# MicroController.net
KiCad netlist of a schematic drawn in Altium Designer
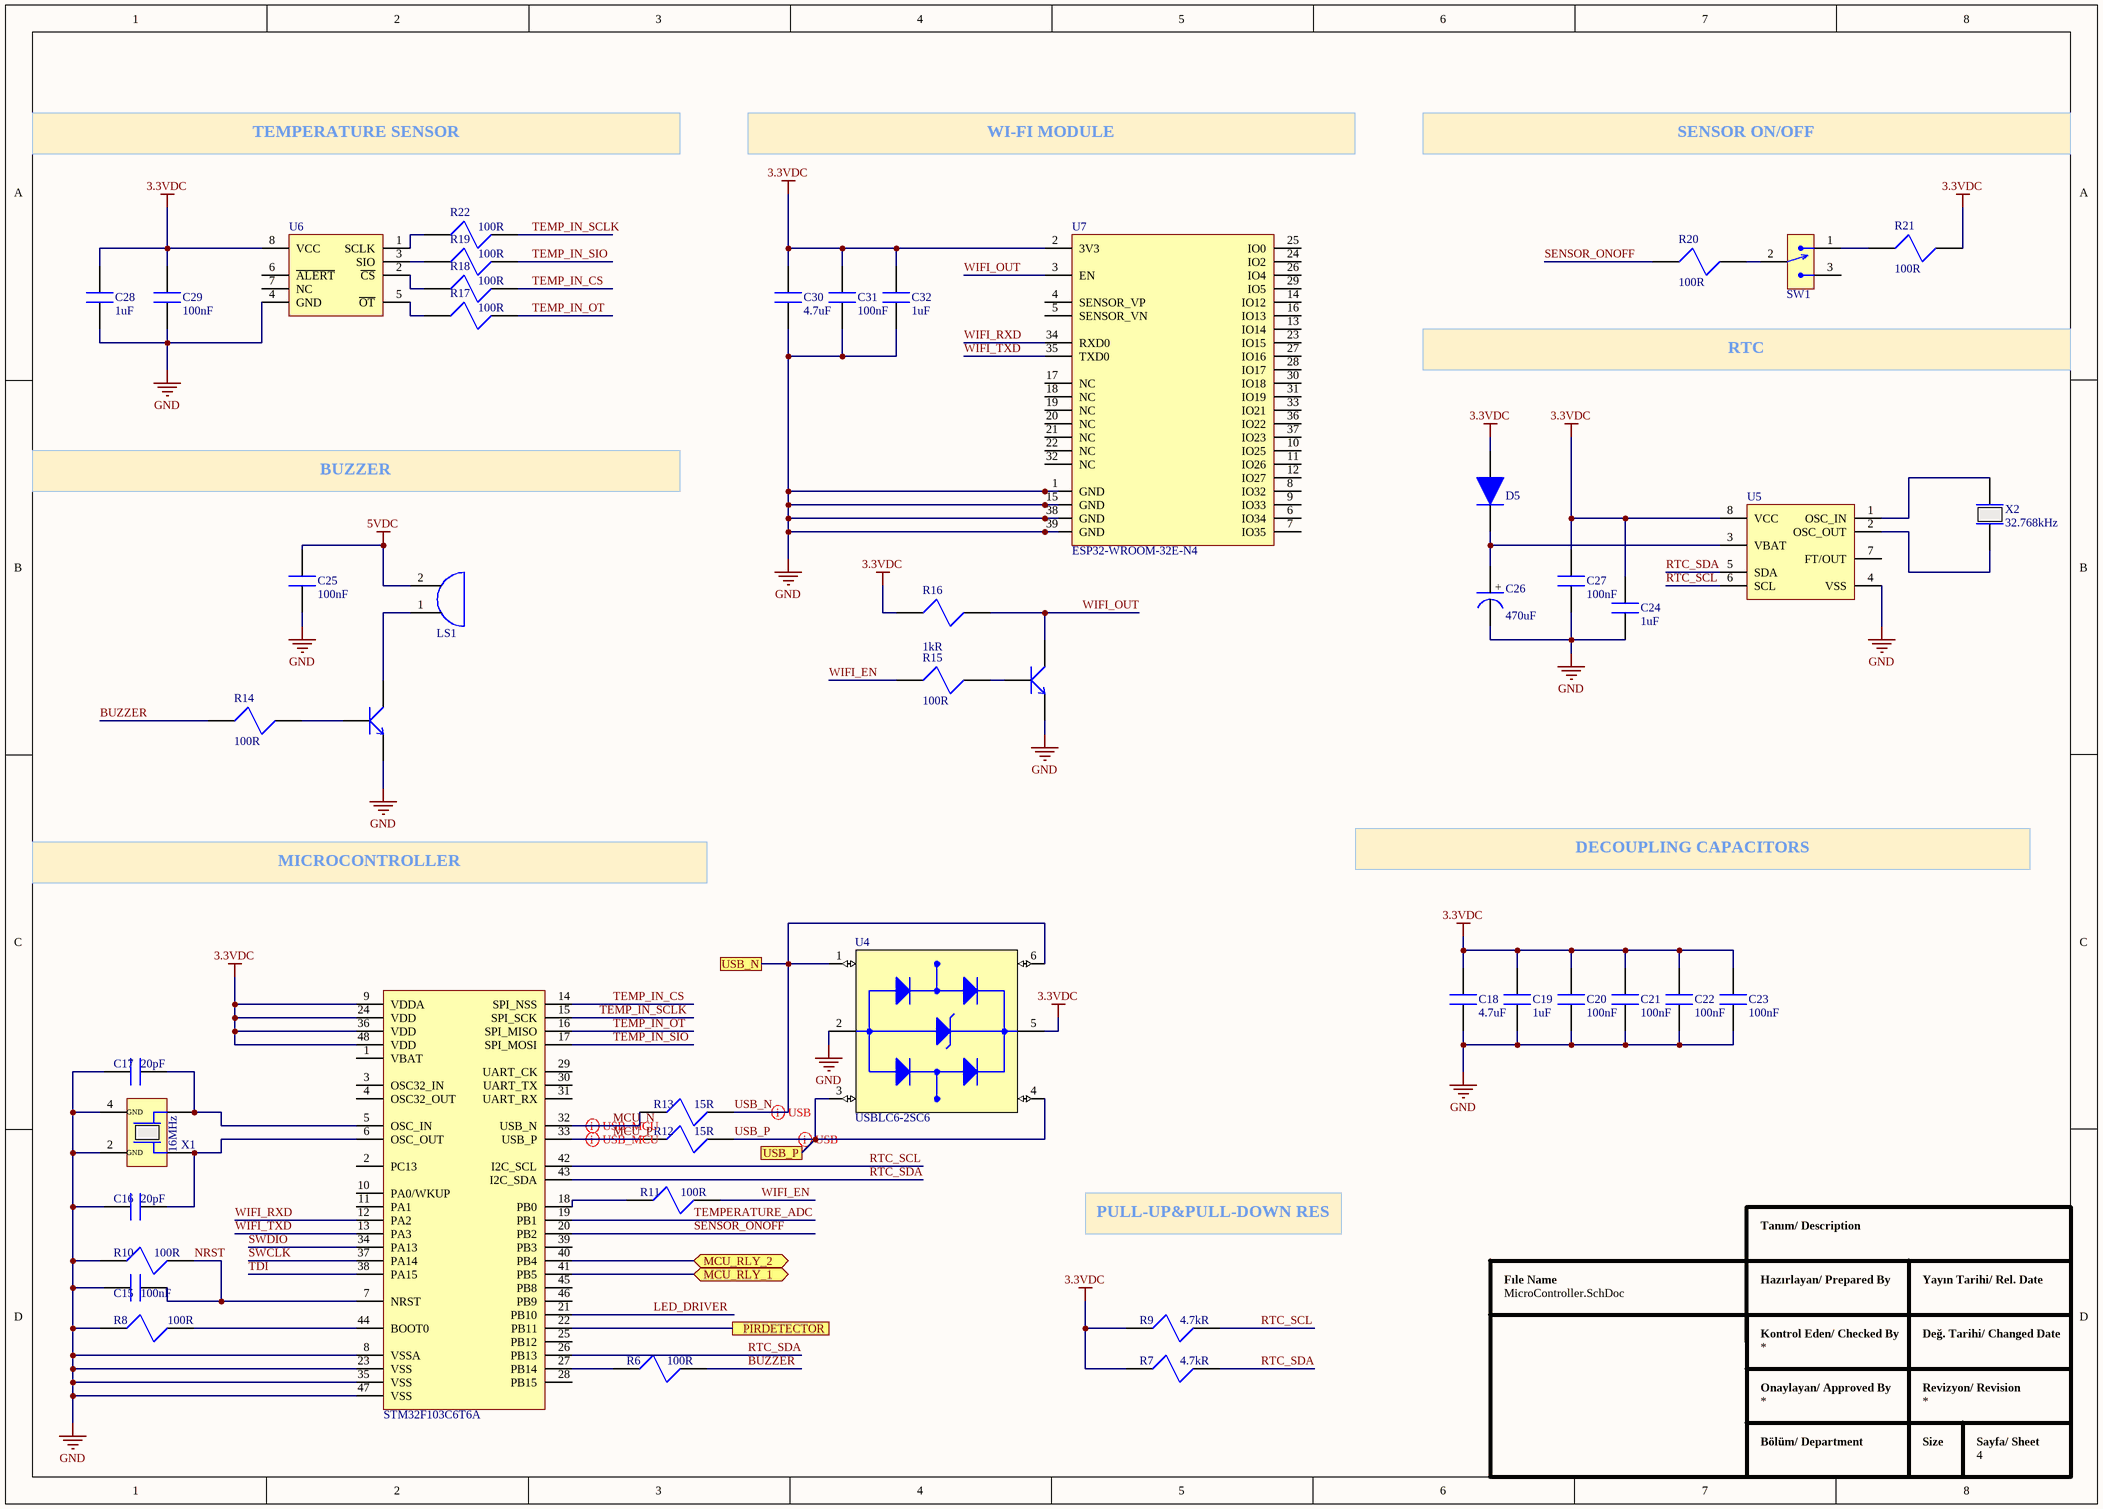
[diagram p0: MicroController.SchDoc]

(export (version "E")
  (design (tool "Eeschema 10.0.6"))
  (components
    (comp (ref "C15")
      (value "C0603C104M5RAC7867")
      (footprint "CAP_0603")
      (description "CAP CER 0.1UF 50V 20% X7R 0603")
      (fields
        (field (name "MANUFACTURER") "KEMET")
        (field (name "MANUFACTURER PART NUMBER") "C0603C104M5RACTU")
        (field (name "CAPACITANCE") "100nF")
        (field (name "DESIGNED BY") "Rumeysa Şahin")
      )
      (libsource (lib "Integrated_Library1") (part "CAP CER 100nF 0603"))
    )
    (comp (ref "C16")
      (value "CL10C200JB8NNNC")
      (footprint "CAP_0603")
      (description "CAP CER 20PF 50V C0G/NP0 0603")
      (fields
        (field (name "MANUFACTURER") "Samsung")
        (field (name "TOLERANCE") "5%")
        (field (name "CAPACITANCE") "20pF")
        (field (name "DESIGNED BY") "Rumeysa Şahin")
      )
      (libsource (lib "Integrated_Library1") (part "CAP CER 20pF 0603"))
    )
    (comp (ref "C17")
      (value "CL10C200JB8NNNC")
      (footprint "CAP_0603")
      (description "CAP CER 20PF 50V C0G/NP0 0603")
      (fields
        (field (name "MANUFACTURER") "Samsung")
        (field (name "TOLERANCE") "5%")
        (field (name "CAPACITANCE") "20pF")
        (field (name "DESIGNED BY") "Rumeysa Şahin")
      )
      (libsource (lib "Integrated_Library1") (part "CAP CER 20pF 0603"))
    )
    (comp (ref "C18")
      (value "CL21A475KAQNNNE")
      (footprint "CAP_0805")
      (description "CAP CER 4.7UF 25V X5R 0805")
      (fields
        (field (name "MANUFACTURER") "Samsung")
        (field (name "TOLERANCE") "10%")
        (field (name "CAPACITANCE") "4.7uF")
        (field (name "DESIGNED BY") "Rumeysa Şahin")
      )
      (libsource (lib "Integrated_Library1") (part "CAP CER 4.7uF 0805"))
    )
    (comp (ref "C19")
      (value "CL21B105KBFNNNE")
      (footprint "CAP_0805")
      (description "CAP CER 1UF 50V X7R 0805")
      (fields
        (field (name "MANUFACTURER") "Samsung")
        (field (name "TOLERANCE") "10%")
        (field (name "CAPACITANCE") "1uF")
        (field (name "DESIGNED BY") "Rumeysa Şahin")
      )
      (libsource (lib "Integrated_Library1") (part "CAP CER 1UF 0805"))
    )
    (comp (ref "C20")
      (value "C0603C104M5RAC7867")
      (footprint "CAP_0603")
      (description "CAP CER 0.1UF 50V 20% X7R 0603")
      (fields
        (field (name "MANUFACTURER") "KEMET")
        (field (name "MANUFACTURER PART NUMBER") "C0603C104M5RACTU")
        (field (name "CAPACITANCE") "100nF")
        (field (name "DESIGNED BY") "Rumeysa Şahin")
      )
      (libsource (lib "Integrated_Library1") (part "CAP CER 100nF 0603"))
    )
    (comp (ref "C21")
      (value "C0603C104M5RAC7867")
      (footprint "CAP_0603")
      (description "CAP CER 0.1UF 50V 20% X7R 0603")
      (fields
        (field (name "MANUFACTURER") "KEMET")
        (field (name "MANUFACTURER PART NUMBER") "C0603C104M5RACTU")
        (field (name "CAPACITANCE") "100nF")
        (field (name "DESIGNED BY") "Rumeysa Şahin")
      )
      (libsource (lib "Integrated_Library1") (part "CAP CER 100nF 0603"))
    )
    (comp (ref "C22")
      (value "C0603C104M5RAC7867")
      (footprint "CAP_0603")
      (description "CAP CER 0.1UF 50V 20% X7R 0603")
      (fields
        (field (name "MANUFACTURER") "KEMET")
        (field (name "MANUFACTURER PART NUMBER") "C0603C104M5RACTU")
        (field (name "CAPACITANCE") "100nF")
        (field (name "DESIGNED BY") "Rumeysa Şahin")
      )
      (libsource (lib "Integrated_Library1") (part "CAP CER 100nF 0603"))
    )
    (comp (ref "C23")
      (value "C0603C104M5RAC7867")
      (footprint "CAP_0603")
      (description "CAP CER 0.1UF 50V 20% X7R 0603")
      (fields
        (field (name "MANUFACTURER") "KEMET")
        (field (name "MANUFACTURER PART NUMBER") "C0603C104M5RACTU")
        (field (name "CAPACITANCE") "100nF")
        (field (name "DESIGNED BY") "Rumeysa Şahin")
      )
      (libsource (lib "Integrated_Library1") (part "CAP CER 100nF 0603"))
    )
    (comp (ref "C24")
      (value "CL21B105KBFNNNE")
      (footprint "CAP_0805")
      (description "CAP CER 1UF 50V X7R 0805")
      (fields
        (field (name "MANUFACTURER") "Samsung")
        (field (name "TOLERANCE") "10%")
        (field (name "CAPACITANCE") "1uF")
        (field (name "DESIGNED BY") "Rumeysa Şahin")
      )
      (libsource (lib "Integrated_Library1") (part "CAP CER 1UF 0805"))
    )
    (comp (ref "C25")
      (value "CL21B104KBCNNNC")
      (footprint "CAP_0805")
      (description "CAP CER 0.1UF 50V X7R 0805")
      (fields
        (field (name "MANUFACTURER") "Samsung")
        (field (name "TOLERANCE") "10%")
        (field (name "CAPACITANCE") "100nF")
        (field (name "DESIGNED BY") "Rumeysa Şahin")
      )
      (libsource (lib "Integrated_Library1") (part "CAP CER 100nF 0805"))
    )
    (comp (ref "C26")
      (value "ESH477M050AH4AA")
      (footprint "ESH477M050AH4AA")
      (description "Cap, 470UF, 50V, Alu Elec, Radial")
      (fields
        (field (name "MANUFACTURER") "KEMET")
        (field (name "TOLERANCE") "20%")
        (field (name "CAPACITANCE") "470uF")
        (field (name "DESIGNED BY") "Rumeysa Şahin")
      )
      (libsource (lib "Integrated_Library1") (part "CAP ALU 470uF"))
    )
    (comp (ref "C27")
      (value "CL21B104KBCNNNC")
      (footprint "CAP_0805")
      (description "CAP CER 0.1UF 50V X7R 0805")
      (fields
        (field (name "MANUFACTURER") "Samsung")
        (field (name "TOLERANCE") "10%")
        (field (name "CAPACITANCE") "100nF")
        (field (name "DESIGNED BY") "Rumeysa Şahin")
      )
      (libsource (lib "Integrated_Library1") (part "CAP CER 100nF 0805"))
    )
    (comp (ref "C28")
      (value "CL21B105KBFNNNE")
      (footprint "CAP_0805")
      (description "CAP CER 1UF 50V X7R 0805")
      (fields
        (field (name "MANUFACTURER") "Samsung")
        (field (name "TOLERANCE") "10%")
        (field (name "CAPACITANCE") "1uF")
        (field (name "DESIGNED BY") "Rumeysa Şahin")
      )
      (libsource (lib "Integrated_Library1") (part "CAP CER 1UF 0805"))
    )
    (comp (ref "C29")
      (value "CL21B104KBCNNNC")
      (footprint "CAP_0805")
      (description "CAP CER 0.1UF 50V X7R 0805")
      (fields
        (field (name "MANUFACTURER") "Samsung")
        (field (name "TOLERANCE") "10%")
        (field (name "CAPACITANCE") "100nF")
        (field (name "DESIGNED BY") "Rumeysa Şahin")
      )
      (libsource (lib "Integrated_Library1") (part "CAP CER 100nF 0805"))
    )
    (comp (ref "C30")
      (value "CL21A475KAQNNNE")
      (footprint "CAP_0805")
      (description "CAP CER 4.7UF 25V X5R 0805")
      (fields
        (field (name "MANUFACTURER") "Samsung")
        (field (name "TOLERANCE") "10%")
        (field (name "CAPACITANCE") "4.7uF")
        (field (name "DESIGNED BY") "Rumeysa Şahin")
      )
      (libsource (lib "Integrated_Library1") (part "CAP CER 4.7uF 0805"))
    )
    (comp (ref "C31")
      (value "CL21B104KBCNNNC")
      (footprint "CAP_0805")
      (description "CAP CER 0.1UF 50V X7R 0805")
      (fields
        (field (name "MANUFACTURER") "Samsung")
        (field (name "TOLERANCE") "10%")
        (field (name "CAPACITANCE") "100nF")
        (field (name "DESIGNED BY") "Rumeysa Şahin")
      )
      (libsource (lib "Integrated_Library1") (part "CAP CER 100nF 0805"))
    )
    (comp (ref "C32")
      (value "CL21B105KBFNNNE")
      (footprint "CAP_0805")
      (description "CAP CER 1UF 50V X7R 0805")
      (fields
        (field (name "MANUFACTURER") "Samsung")
        (field (name "TOLERANCE") "10%")
        (field (name "CAPACITANCE") "1uF")
        (field (name "DESIGNED BY") "Rumeysa Şahin")
      )
      (libsource (lib "Integrated_Library1") (part "CAP CER 1UF 0805"))
    )
    (comp (ref "D5")
      (value "1N4148WS")
      (footprint "SOD323F")
      (description "VR=75V IF=150mA Trr=4ns P=200mW")
      (fields
        (field (name "MANUFACTURER") "ON Semiconductor / Fairchild")
        (field (name "DESIGNED BY") "Rumeysa Şahin")
      )
      (libsource (lib "Integrated_Library1") (part "1N4148WS"))
    )
    (comp (ref "LS1")
      (value "CMI-9605IC-0580T")
      (footprint "CMI-9605IC-0580T")
      (description "Audio Buzzer Magnetic 3VDC 7VDC 30mA 5VDC 85dB 2600Hz to 2800Hz Through Hole Pin Box")
      (fields (field (name "MANUFACTURER") "CUI Devices") (field (name "DESIGNED BY") "Rumeysa Şahin"))
      (libsource (lib "Integrated_Library1") (part "CMI-9605IC-0580T"))
    )
    (comp (ref "Q3")
      (value "MMBT3904-7-F")
      (footprint "SOT23F")
      (description "NPN Ic=200mA Vceo=40V hfe=100~300 fT=310MHz P=300mW SOT-23")
      (fields (field (name "MANUFACTURER") "Diodes Zetex") (field (name "DESIGNED BY") "Rumeysa Şahin"))
      (libsource (lib "Integrated_Library1") (part "MMBT3904-7-F"))
    )
    (comp (ref "Q4")
      (value "MMBT3904-7-F")
      (footprint "SOT23F")
      (description "NPN Ic=200mA Vceo=40V hfe=100~300 fT=310MHz P=300mW SOT-23")
      (fields (field (name "MANUFACTURER") "Diodes Zetex") (field (name "DESIGNED BY") "Rumeysa Şahin"))
      (libsource (lib "Integrated_Library1") (part "MMBT3904-7-F"))
    )
    (comp (ref "R6")
      (value "RC0603JR-13100RL")
      (footprint "RES_0603")
      (description "Res Thick Film 0603 100 Ohm 5% 0.1W(1/10W) ±100ppm/C Pad SMD T/R")
      (fields
        (field (name "MANUFACTURER") "Yageo")
        (field (name "TOLERANCE") "5%")
        (field (name "RESISTANCE") "100R")
        (field (name "DESIGNED BY") "Rumeysa Şahin")
      )
      (libsource (lib "Integrated_Library1") (part "RES 100 OHM 0603"))
    )
    (comp (ref "R7")
      (value "RC0603FR-074K7L")
      (footprint "RES_0603")
      (description "Res Thick Film 0603 4.7K Ohm 1% 1/10W ±100ppm/°C Molded SMD Paper T/R")
      (fields
        (field (name "MANUFACTURER") "Yageo")
        (field (name "TOLERANCE") "1%")
        (field (name "RESISTANCE") "4.7kR")
        (field (name "DESIGNED BY") "Rumeysa Şahin")
      )
      (libsource (lib "Integrated_Library1") (part "RES 4K7R OHM 0603"))
    )
    (comp (ref "R8")
      (value "RC0603JR-13100RL")
      (footprint "RES_0603")
      (description "Res Thick Film 0603 100 Ohm 5% 0.1W(1/10W) ±100ppm/C Pad SMD T/R")
      (fields
        (field (name "MANUFACTURER") "Yageo")
        (field (name "TOLERANCE") "5%")
        (field (name "RESISTANCE") "100R")
        (field (name "DESIGNED BY") "Rumeysa Şahin")
      )
      (libsource (lib "Integrated_Library1") (part "RES 100 OHM 0603"))
    )
    (comp (ref "R9")
      (value "RC0603FR-074K7L")
      (footprint "RES_0603")
      (description "Res Thick Film 0603 4.7K Ohm 1% 1/10W ±100ppm/°C Molded SMD Paper T/R")
      (fields
        (field (name "MANUFACTURER") "Yageo")
        (field (name "TOLERANCE") "1%")
        (field (name "RESISTANCE") "4.7kR")
        (field (name "DESIGNED BY") "Rumeysa Şahin")
      )
      (libsource (lib "Integrated_Library1") (part "RES 4K7R OHM 0603"))
    )
    (comp (ref "R10")
      (value "RC0603JR-13100RL")
      (footprint "RES_0603")
      (description "Res Thick Film 0603 100 Ohm 5% 0.1W(1/10W) ±100ppm/C Pad SMD T/R")
      (fields
        (field (name "MANUFACTURER") "Yageo")
        (field (name "TOLERANCE") "5%")
        (field (name "RESISTANCE") "100R")
        (field (name "DESIGNED BY") "Rumeysa Şahin")
      )
      (libsource (lib "Integrated_Library1") (part "RES 100 OHM 0603"))
    )
    (comp (ref "R11")
      (value "RC0603JR-13100RL")
      (footprint "RES_0603")
      (description "Res Thick Film 0603 100 Ohm 5% 0.1W(1/10W) ±100ppm/C Pad SMD T/R")
      (fields
        (field (name "MANUFACTURER") "Yageo")
        (field (name "TOLERANCE") "5%")
        (field (name "RESISTANCE") "100R")
        (field (name "DESIGNED BY") "Rumeysa Şahin")
      )
      (libsource (lib "Integrated_Library1") (part "RES 100 OHM 0603"))
    )
    (comp (ref "R12")
      (value "RES 15 OHM 0603")
      (footprint "RES_0603")
      (description "Res Thick Film 0603 15 Ohm 5%")
      (fields
        (field (name "MANUFACTURER") "Yageo")
        (field (name "MANUFACTURER PART NUMBER") "RC0603JR-0715RL")
        (field (name "RESISTANCE") "15R")
        (field (name "DESIGNED BY") "Rumeysa Şahin")
      )
      (libsource (lib "Integrated_Library1") (part "RES 15 OHM 0603"))
    )
    (comp (ref "R13")
      (value "RES 15 OHM 0603")
      (footprint "RES_0603")
      (description "Res Thick Film 0603 15 Ohm 5%")
      (fields
        (field (name "MANUFACTURER") "Yageo")
        (field (name "MANUFACTURER PART NUMBER") "RC0603JR-0715RL")
        (field (name "RESISTANCE") "15R")
        (field (name "DESIGNED BY") "Rumeysa Şahin")
      )
      (libsource (lib "Integrated_Library1") (part "RES 15 OHM 0603"))
    )
    (comp (ref "R14")
      (value "RC0603JR-13100RL")
      (footprint "RES_0603")
      (description "Res Thick Film 0603 100 Ohm 5% 0.1W(1/10W) ±100ppm/C Pad SMD T/R")
      (fields
        (field (name "MANUFACTURER") "Yageo")
        (field (name "TOLERANCE") "5%")
        (field (name "RESISTANCE") "100R")
        (field (name "DESIGNED BY") "Rumeysa Şahin")
      )
      (libsource (lib "Integrated_Library1") (part "RES 100 OHM 0603"))
    )
    (comp (ref "R15")
      (value "RC0603JR-13100RL")
      (footprint "RES_0603")
      (description "Res Thick Film 0603 100 Ohm 5% 0.1W(1/10W) ±100ppm/C Pad SMD T/R")
      (fields
        (field (name "MANUFACTURER") "Yageo")
        (field (name "TOLERANCE") "5%")
        (field (name "RESISTANCE") "100R")
        (field (name "DESIGNED BY") "Rumeysa Şahin")
      )
      (libsource (lib "Integrated_Library1") (part "RES 100 OHM 0603"))
    )
    (comp (ref "R16")
      (value "RC0603FR-071KL")
      (footprint "RES_0603")
      (description "Res Thick Film 0603 1K Ohm 1% 1/10W ±100ppm/°C Molded SMD SMD Paper T/R")
      (fields
        (field (name "MANUFACTURER") "Yageo")
        (field (name "TOLERANCE") "1%")
        (field (name "RESISTANCE") "1kR")
        (field (name "DESIGNED BY") "Rumeysa Şahin")
      )
      (libsource (lib "Integrated_Library1") (part "RES 1K OHM 0603"))
    )
    (comp (ref "R17")
      (value "RC0603JR-13100RL")
      (footprint "RES_0603")
      (description "Res Thick Film 0603 100 Ohm 5% 0.1W(1/10W) ±100ppm/C Pad SMD T/R")
      (fields
        (field (name "MANUFACTURER") "Yageo")
        (field (name "TOLERANCE") "5%")
        (field (name "RESISTANCE") "100R")
        (field (name "DESIGNED BY") "Rumeysa Şahin")
      )
      (libsource (lib "Integrated_Library1") (part "RES 100 OHM 0603"))
    )
    (comp (ref "R18")
      (value "RC0603JR-13100RL")
      (footprint "RES_0603")
      (description "Res Thick Film 0603 100 Ohm 5% 0.1W(1/10W) ±100ppm/C Pad SMD T/R")
      (fields
        (field (name "MANUFACTURER") "Yageo")
        (field (name "TOLERANCE") "5%")
        (field (name "RESISTANCE") "100R")
        (field (name "DESIGNED BY") "Rumeysa Şahin")
      )
      (libsource (lib "Integrated_Library1") (part "RES 100 OHM 0603"))
    )
    (comp (ref "R19")
      (value "RC0603JR-13100RL")
      (footprint "RES_0603")
      (description "Res Thick Film 0603 100 Ohm 5% 0.1W(1/10W) ±100ppm/C Pad SMD T/R")
      (fields
        (field (name "MANUFACTURER") "Yageo")
        (field (name "TOLERANCE") "5%")
        (field (name "RESISTANCE") "100R")
        (field (name "DESIGNED BY") "Rumeysa Şahin")
      )
      (libsource (lib "Integrated_Library1") (part "RES 100 OHM 0603"))
    )
    (comp (ref "R20")
      (value "RC0603JR-13100RL")
      (footprint "RES_0603")
      (description "Res Thick Film 0603 100 Ohm 5% 0.1W(1/10W) ±100ppm/C Pad SMD T/R")
      (fields
        (field (name "MANUFACTURER") "Yageo")
        (field (name "TOLERANCE") "5%")
        (field (name "RESISTANCE") "100R")
        (field (name "DESIGNED BY") "Rumeysa Şahin")
      )
      (libsource (lib "Integrated_Library1") (part "RES 100 OHM 0603"))
    )
    (comp (ref "R21")
      (value "RC0603JR-13100RL")
      (footprint "RES_0603")
      (description "Res Thick Film 0603 100 Ohm 5% 0.1W(1/10W) ±100ppm/C Pad SMD T/R")
      (fields
        (field (name "MANUFACTURER") "Yageo")
        (field (name "TOLERANCE") "5%")
        (field (name "RESISTANCE") "100R")
        (field (name "DESIGNED BY") "Rumeysa Şahin")
      )
      (libsource (lib "Integrated_Library1") (part "RES 100 OHM 0603"))
    )
    (comp (ref "R22")
      (value "RC0603JR-13100RL")
      (footprint "RES_0603")
      (description "Res Thick Film 0603 100 Ohm 5% 0.1W(1/10W) ±100ppm/C Pad SMD T/R")
      (fields
        (field (name "MANUFACTURER") "Yageo")
        (field (name "TOLERANCE") "5%")
        (field (name "RESISTANCE") "100R")
        (field (name "DESIGNED BY") "Rumeysa Şahin")
      )
      (libsource (lib "Integrated_Library1") (part "RES 100 OHM 0603"))
    )
    (comp (ref "SW1")
      (value "EG1215AA")
      (footprint "EG1215AA")
      (description "Slide Switch, SPDT, 0.025A, 24V, SMD")
      (fields (field (name "MANUFACTURER") "E-Switch") (field (name "TOLERANCE") "4.95%"))
      (libsource (lib "Integrated_Library1") (part "EG1215AA"))
    )
    (comp (ref "U3")
      (value "STM32F103C6T6A")
      (footprint "LQFP-48")
      (description "MCU 32-bit STM32F ARM Cortex M3 RISC 32KB Flash 2.5V/3.3V 48-Pin LQFP Tray")
      (fields (field (name "MANUFACTURER") "STMicroelectronics") (field (name "DESIGNED BY") "Rumeysa Şahin"))
      (libsource (lib "Integrated_Library1") (part "STM32F103C6T6A"))
    )
    (comp (ref "U4")
      (value "USBLC6-2SC6")
      (footprint "SOT-23-6L")
      (description "TVS DIODE 5.25VWM 17VC SOT23-6")
      (fields (field (name "MANUFACTURER") "STMicroelectronics") (field (name "DESIGNED BY") "Rumeysa Şahin"))
      (libsource (lib "Integrated_Library1") (part "USB PROTECTION"))
    )
    (comp (ref "U5")
      (value "M41T0M6F")
      (footprint "SOIC-8")
      (description "M41T0 Series 2 to 5.5 V Serial I2C Real Time Clock Surface Mount - SOIC-8")
      (fields (field (name "MANUFACTURER") "STMicroelectronics") (field (name "DESIGNED BY") "Rumeysa Şahin"))
      (libsource (lib "Integrated_Library1") (part "M41T0M6F"))
    )
    (comp (ref "U6")
      (value "MAX6662MSA+")
      (footprint "SOIC-8")
      (description "Temp Sensor Digital Serial (3-Wire, SPI) 8-Pin SOIC N Tube")
      (fields (field (name "MANUFACTURER") "Maxim") (field (name "DESIGNED BY") "Rumeysa Şahin"))
      (libsource (lib "Integrated_Library1") (part "MAX6662MSA+"))
    )
    (comp (ref "U7")
      (value "ESP32-WROOM-32E-N4")
      (footprint "ESP32-32E")
      (description "Rx Txrx Mod Wifi Trace Ant SMD")
      (fields
        (field (name "MANUFACTURER") "Espressif Systems")
        (field (name "MANUFACTURER PART NUMBER") "ESP32-WROOM-32E(M113EH3200PH3Q0)")
        (field (name "DESIGNED BY") "Rumeysa Şahin")
      )
      (libsource (lib "Integrated_Library1") (part "ESP32-WROOM-32E-N4"))
    )
    (comp (ref "X1")
      (value "ECS-160-20-30B-TR")
      (footprint "ECS")
      (description "Crystal 16MHz ±30ppm (Tol) ±50ppm (Stability) 20pF FUND 50Ohm 4-Pin Mini-SMD T/R")
      (fields
        (field (name "MANUFACTURER") "ECS International")
        (field (name "TOLERANCE") "50ppm")
        (field (name "FREQUENCY") "16MHz")
        (field (name "DESIGNED BY") "Rumeysa Şahin")
      )
      (libsource (lib "Integrated_Library1") (part "CRYSTAL 16MHZ"))
    )
    (comp (ref "X2")
      (value "ABS05-32.768KHZ-T")
      (footprint "ABS05")
      (description "Crystal 0.032768MHz ±20ppm (Tol) 12.5pF Flexural 90000Ohm 2-Pin CSMD T/R")
      (fields
        (field (name "MANUFACTURER") "Abracon")
        (field (name "TOLERANCE") "20ppm")
        (field (name "FREQUENCY") "32.768kHz")
        (field (name "DESIGNED BY") "Rumeysa Şahin")
      )
      (libsource (lib "Integrated_Library1") (part "CRYSTAL 32768kHZ"))
    )
  )
  (nets
    (net (code "1") (name "/BUZZER") (class "Default")
      (node (ref "R14") (pin "1") (pintype "passive"))
      (node (ref "R6") (pin "2") (pinfunction "2_2") (pintype "passive"))
    )
    (net (code "2") (name "/LED_DRIVER") (class "Default")
      (node (ref "U3") (pin "21") (pinfunction "PB10_21") (pintype "passive"))
    )
    (net (code "3") (name "/MCU_N") (class "Default")
      (node (ref "R13") (pin "1") (pintype "passive"))
      (node (ref "U3") (pin "32") (pinfunction "USB_N_32") (pintype "passive"))
    )
    (net (code "4") (name "/MCU_P") (class "Default")
      (node (ref "R12") (pin "1") (pintype "passive"))
      (node (ref "U3") (pin "33") (pinfunction "USB_P_33") (pintype "passive"))
    )
    (net (code "5") (name "/MCU_RLY_1") (class "Default")
      (node (ref "U3") (pin "41") (pinfunction "PB5_41") (pintype "passive"))
    )
    (net (code "6") (name "/MCU_RLY_2") (class "Default")
      (node (ref "U3") (pin "40") (pinfunction "PB4_40") (pintype "passive"))
    )
    (net (code "7") (name "/NRST") (class "Default")
      (node (ref "C15") (pin "1") (pinfunction "1_1") (pintype "passive"))
      (node (ref "R10") (pin "2") (pinfunction "2_2") (pintype "passive"))
      (node (ref "U3") (pin "7") (pinfunction "NRST_7") (pintype "passive"))
    )
    (net (code "8") (name "/PIRDETECTOR") (class "Default")
      (node (ref "U3") (pin "22") (pinfunction "PB11_22") (pintype "passive"))
    )
    (net (code "9") (name "/RTC_SCL") (class "Default")
      (node (ref "R9") (pin "1") (pintype "passive"))
      (node (ref "U3") (pin "42") (pinfunction "I2C_SCL_42") (pintype "passive"))
      (node (ref "U5") (pin "6") (pinfunction "SCL_6") (pintype "passive"))
    )
    (net (code "10") (name "/RTC_SDA") (class "Default")
      (node (ref "R7") (pin "1") (pintype "passive"))
      (node (ref "U3") (pin "26") (pinfunction "PB13_26") (pintype "passive"))
      (node (ref "U3") (pin "43") (pinfunction "I2C_SDA_43") (pintype "passive"))
      (node (ref "U5") (pin "5") (pinfunction "SDA_5") (pintype "passive"))
    )
    (net (code "11") (name "/SENSOR_ONOFF") (class "Default")
      (node (ref "R20") (pin "1") (pintype "passive"))
      (node (ref "U3") (pin "20") (pinfunction "PB2_20") (pintype "passive"))
    )
    (net (code "12") (name "/SWCLK") (class "Default")
      (node (ref "U3") (pin "37") (pinfunction "PA14_37") (pintype "passive"))
    )
    (net (code "13") (name "/SWDIO") (class "Default")
      (node (ref "U3") (pin "34") (pinfunction "PA13_34") (pintype "passive"))
    )
    (net (code "14") (name "/TDI") (class "Default")
      (node (ref "U3") (pin "38") (pinfunction "PA15_38") (pintype "passive"))
    )
    (net (code "15") (name "/TEMPERATURE_ADC") (class "Default")
      (node (ref "U3") (pin "19") (pinfunction "PB1_19") (pintype "passive"))
    )
    (net (code "16") (name "/TEMP_IN_CS") (class "Default")
      (node (ref "R18") (pin "2") (pinfunction "2_2") (pintype "passive"))
      (node (ref "U3") (pin "14") (pinfunction "SPI_NSS_14") (pintype "passive"))
    )
    (net (code "17") (name "/TEMP_IN_OT") (class "Default")
      (node (ref "R17") (pin "2") (pinfunction "2_2") (pintype "passive"))
      (node (ref "U3") (pin "16") (pinfunction "SPI_MISO_16") (pintype "passive"))
    )
    (net (code "18") (name "/TEMP_IN_SCLK") (class "Default")
      (node (ref "R22") (pin "2") (pinfunction "2_2") (pintype "passive"))
      (node (ref "U3") (pin "15") (pinfunction "SPI_SCK_15") (pintype "passive"))
    )
    (net (code "19") (name "/TEMP_IN_SIO") (class "Default")
      (node (ref "R19") (pin "2") (pinfunction "2_2") (pintype "passive"))
      (node (ref "U3") (pin "17") (pinfunction "SPI_MOSI_17") (pintype "passive"))
    )
    (net (code "20") (name "/USB_N") (class "Default")
      (node (ref "R13") (pin "2") (pinfunction "2_2") (pintype "passive"))
      (node (ref "U4") (pin "1") (pinfunction "I/O1_IN_1") (pintype "bidirectional"))
      (node (ref "U4") (pin "6") (pinfunction "I/O1_OUT_6") (pintype "bidirectional"))
    )
    (net (code "21") (name "/USB_P") (class "Default")
      (node (ref "R12") (pin "2") (pinfunction "2_2") (pintype "passive"))
      (node (ref "U4") (pin "3") (pinfunction "I/O2_IN_3") (pintype "bidirectional"))
      (node (ref "U4") (pin "4") (pinfunction "I/O2_OUT_4") (pintype "bidirectional"))
    )
    (net (code "22") (name "/WIFI_EN") (class "Default")
      (node (ref "R11") (pin "2") (pinfunction "2_2") (pintype "passive"))
      (node (ref "R15") (pin "1") (pintype "passive"))
    )
    (net (code "23") (name "/WIFI_OUT") (class "Default")
      (node (ref "Q4") (pin "3") (pinfunction "C_3") (pintype "power_in"))
      (node (ref "R16") (pin "2") (pinfunction "2_2") (pintype "passive"))
      (node (ref "U7") (pin "3") (pinfunction "EN_3") (pintype "passive"))
    )
    (net (code "24") (name "/WIFI_RXD") (class "Default")
      (node (ref "U3") (pin "12") (pinfunction "PA2_12") (pintype "passive"))
      (node (ref "U7") (pin "34") (pinfunction "RXD0_34") (pintype "passive"))
    )
    (net (code "25") (name "/WIFI_TXD") (class "Default")
      (node (ref "U3") (pin "13") (pinfunction "PA3_13") (pintype "passive"))
      (node (ref "U7") (pin "35") (pinfunction "TXD0_35") (pintype "passive"))
    )
    (net (code "26") (name "3.3VDC") (class "Default")
      (node (ref "C18") (pin "2") (pinfunction "2_2") (pintype "passive"))
      (node (ref "C19") (pin "2") (pinfunction "2_2") (pintype "passive"))
      (node (ref "C20") (pin "2") (pinfunction "2_2") (pintype "passive"))
      (node (ref "C21") (pin "2") (pinfunction "2_2") (pintype "passive"))
      (node (ref "C22") (pin "2") (pinfunction "2_2") (pintype "passive"))
      (node (ref "C23") (pin "2") (pinfunction "2_2") (pintype "passive"))
      (node (ref "C24") (pin "2") (pinfunction "2_2") (pintype "passive"))
      (node (ref "C27") (pin "2") (pinfunction "2_2") (pintype "passive"))
      (node (ref "C28") (pin "2") (pinfunction "2_2") (pintype "passive"))
      (node (ref "C29") (pin "2") (pinfunction "2_2") (pintype "passive"))
      (node (ref "C30") (pin "2") (pinfunction "2_2") (pintype "passive"))
      (node (ref "C31") (pin "2") (pinfunction "2_2") (pintype "passive"))
      (node (ref "C32") (pin "2") (pinfunction "2_2") (pintype "passive"))
      (node (ref "D5") (pin "2") (pinfunction "2_2") (pintype "power_in"))
      (node (ref "R16") (pin "1") (pintype "passive"))
      (node (ref "R21") (pin "2") (pinfunction "2_2") (pintype "passive"))
      (node (ref "R7") (pin "2") (pinfunction "2_2") (pintype "passive"))
      (node (ref "R9") (pin "2") (pinfunction "2_2") (pintype "passive"))
      (node (ref "U3") (pin "24") (pinfunction "VDD_24") (pintype "passive"))
      (node (ref "U3") (pin "36") (pinfunction "VDD_36") (pintype "passive"))
      (node (ref "U3") (pin "48") (pinfunction "VDD_48") (pintype "passive"))
      (node (ref "U3") (pin "9") (pinfunction "VDDA_9") (pintype "passive"))
      (node (ref "U4") (pin "5") (pinfunction "VBUS_5") (pintype "power_in"))
      (node (ref "U5") (pin "8") (pinfunction "VCC_8") (pintype "passive"))
      (node (ref "U6") (pin "8") (pinfunction "VCC_8") (pintype "passive"))
      (node (ref "U7") (pin "2") (pinfunction "3V3_2") (pintype "passive"))
    )
    (net (code "27") (name "5VDC") (class "Default")
      (node (ref "C25") (pin "2") (pinfunction "2_2") (pintype "passive"))
      (node (ref "LS1") (pin "2") (pinfunction "2_2") (pintype "passive"))
    )
    (net (code "28") (name "GND") (class "Default")
      (node (ref "C15") (pin "2") (pinfunction "2_2") (pintype "passive"))
      (node (ref "C16") (pin "2") (pinfunction "2_2") (pintype "passive"))
      (node (ref "C17") (pin "2") (pinfunction "2_2") (pintype "passive"))
      (node (ref "C18") (pin "1") (pinfunction "1_1") (pintype "passive"))
      (node (ref "C19") (pin "1") (pinfunction "1_1") (pintype "passive"))
      (node (ref "C20") (pin "1") (pinfunction "1_1") (pintype "passive"))
      (node (ref "C21") (pin "1") (pinfunction "1_1") (pintype "passive"))
      (node (ref "C22") (pin "1") (pinfunction "1_1") (pintype "passive"))
      (node (ref "C23") (pin "1") (pinfunction "1_1") (pintype "passive"))
      (node (ref "C24") (pin "1") (pinfunction "1_1") (pintype "passive"))
      (node (ref "C25") (pin "1") (pinfunction "1_1") (pintype "passive"))
      (node (ref "C26") (pin "2") (pinfunction "2_2") (pintype "passive"))
      (node (ref "C27") (pin "1") (pinfunction "1_1") (pintype "passive"))
      (node (ref "C28") (pin "1") (pinfunction "1_1") (pintype "passive"))
      (node (ref "C29") (pin "1") (pinfunction "1_1") (pintype "passive"))
      (node (ref "C30") (pin "1") (pinfunction "1_1") (pintype "passive"))
      (node (ref "C31") (pin "1") (pinfunction "1_1") (pintype "passive"))
      (node (ref "C32") (pin "1") (pinfunction "1_1") (pintype "passive"))
      (node (ref "Q3") (pin "2") (pinfunction "E_2") (pintype "power_in"))
      (node (ref "Q4") (pin "2") (pinfunction "E_2") (pintype "power_in"))
      (node (ref "R10") (pin "1") (pintype "passive"))
      (node (ref "R8") (pin "1") (pintype "passive"))
      (node (ref "U3") (pin "23") (pinfunction "VSS_23") (pintype "passive"))
      (node (ref "U3") (pin "35") (pinfunction "VSS_35") (pintype "passive"))
      (node (ref "U3") (pin "47") (pinfunction "VSS_47") (pintype "passive"))
      (node (ref "U3") (pin "8") (pinfunction "VSSA_8") (pintype "passive"))
      (node (ref "U4") (pin "2") (pinfunction "GND_2") (pintype "power_in"))
      (node (ref "U5") (pin "4") (pinfunction "VSS_4") (pintype "passive"))
      (node (ref "U6") (pin "4") (pinfunction "GND_4") (pintype "passive"))
      (node (ref "U7") (pin "1") (pinfunction "GND_1") (pintype "passive"))
      (node (ref "U7") (pin "15") (pinfunction "GND_15") (pintype "passive"))
      (node (ref "U7") (pin "38") (pinfunction "GND_38") (pintype "passive"))
      (node (ref "U7") (pin "39") (pinfunction "GND_39") (pintype "passive"))
      (node (ref "X1") (pin "2") (pinfunction "GND_2") (pintype "passive"))
      (node (ref "X1") (pin "4") (pinfunction "GND_4") (pintype "passive"))
    )
    (net (code "29") (name "Net-(Q3-B)") (class "Default")
      (node (ref "Q3") (pin "1") (pinfunction "B_1") (pintype "power_in"))
      (node (ref "R14") (pin "2") (pinfunction "2_2") (pintype "passive"))
    )
    (net (code "30") (name "Net-(Q3-C)") (class "Default")
      (node (ref "LS1") (pin "1") (pinfunction "1_1") (pintype "passive"))
      (node (ref "Q3") (pin "3") (pinfunction "C_3") (pintype "power_in"))
    )
    (net (code "31") (name "Net-(Q4-B)") (class "Default")
      (node (ref "Q4") (pin "1") (pinfunction "B_1") (pintype "power_in"))
      (node (ref "R15") (pin "2") (pinfunction "2_2") (pintype "passive"))
    )
    (net (code "32") (name "Net-(R20-Pad2)") (class "Default")
      (node (ref "R20") (pin "2") (pinfunction "2_2") (pintype "passive"))
      (node (ref "SW1") (pin "2") (pinfunction "2_2") (pintype "passive"))
    )
    (net (code "33") (name "Net-(R21-Pad1)") (class "Default")
      (node (ref "R21") (pin "1") (pintype "passive"))
      (node (ref "SW1") (pin "1") (pinfunction "1_1") (pintype "passive"))
    )
    (net (code "34") (name "Net-(U3-BOOT0)") (class "Default")
      (node (ref "R8") (pin "2") (pinfunction "2_2") (pintype "passive"))
      (node (ref "U3") (pin "44") (pinfunction "BOOT0_44") (pintype "passive"))
    )
    (net (code "35") (name "Net-(U3-OSC_IN)") (class "Default")
      (node (ref "C17") (pin "1") (pinfunction "1_1") (pintype "passive"))
      (node (ref "U3") (pin "5") (pinfunction "OSC_IN_5") (pintype "passive"))
      (node (ref "X1") (pin "3") (pinfunction "3_3") (pintype "passive"))
    )
    (net (code "36") (name "Net-(U3-OSC_OUT)") (class "Default")
      (node (ref "C16") (pin "1") (pinfunction "1_1") (pintype "passive"))
      (node (ref "U3") (pin "6") (pinfunction "OSC_OUT_6") (pintype "passive"))
      (node (ref "X1") (pin "1") (pinfunction "1_1") (pintype "passive"))
    )
    (net (code "37") (name "Net-(U3-PB0)") (class "Default")
      (node (ref "R11") (pin "1") (pintype "passive"))
      (node (ref "U3") (pin "18") (pinfunction "PB0_18") (pintype "passive"))
    )
    (net (code "38") (name "Net-(U3-PB14)") (class "Default")
      (node (ref "R6") (pin "1") (pintype "passive"))
      (node (ref "U3") (pin "27") (pinfunction "PB14_27") (pintype "passive"))
    )
    (net (code "39") (name "Net-(U5-OSC_IN)") (class "Default")
      (node (ref "U5") (pin "1") (pinfunction "OSC_IN_1") (pintype "passive"))
      (node (ref "X2") (pin "2") (pinfunction "2_2") (pintype "passive"))
    )
    (net (code "40") (name "Net-(U5-OSC_OUT)") (class "Default")
      (node (ref "U5") (pin "2") (pinfunction "OSC_OUT_2") (pintype "passive"))
      (node (ref "X2") (pin "1") (pinfunction "1_1") (pintype "passive"))
    )
    (net (code "41") (name "Net-(U5-VBAT)") (class "Default")
      (node (ref "C26") (pin "1") (pinfunction "1_1") (pintype "passive"))
      (node (ref "D5") (pin "1") (pinfunction "1_1") (pintype "power_in"))
      (node (ref "U5") (pin "3") (pinfunction "VBAT_3") (pintype "passive"))
    )
    (net (code "42") (name "Net-(U6-SCLK)") (class "Default")
      (node (ref "R22") (pin "1") (pintype "passive"))
      (node (ref "U6") (pin "1") (pinfunction "SCLK_1") (pintype "passive"))
    )
    (net (code "43") (name "Net-(U6-SIO)") (class "Default")
      (node (ref "R19") (pin "1") (pintype "passive"))
      (node (ref "U6") (pin "3") (pinfunction "SIO_3") (pintype "passive"))
    )
    (net (code "44") (name "Net-(U6-~{CS})") (class "Default")
      (node (ref "R18") (pin "1") (pintype "passive"))
      (node (ref "U6") (pin "2") (pinfunction "~{CS}_2") (pintype "passive"))
    )
    (net (code "45") (name "Net-(U6-~{OT})") (class "Default")
      (node (ref "R17") (pin "1") (pintype "passive"))
      (node (ref "U6") (pin "5") (pinfunction "~{OT}_5") (pintype "passive"))
    )
    (net (code "46") (name "unconnected-(SW1-Pad3)") (class "Default")
      (node (ref "SW1") (pin "3") (pinfunction "3_3") (pintype "passive"))
    )
    (net (code "47") (name "unconnected-(U3-OSC32_IN-Pad3)") (class "Default")
      (node (ref "U3") (pin "3") (pinfunction "OSC32_IN_3") (pintype "passive"))
    )
    (net (code "48") (name "unconnected-(U3-OSC32_OUT-Pad4)") (class "Default")
      (node (ref "U3") (pin "4") (pinfunction "OSC32_OUT_4") (pintype "passive"))
    )
    (net (code "49") (name "unconnected-(U3-PA0{slash}WKUP-Pad10)") (class "Default")
      (node (ref "U3") (pin "10") (pinfunction "PA0/WKUP_10") (pintype "passive"))
    )
    (net (code "50") (name "unconnected-(U3-PA1-Pad11)") (class "Default")
      (node (ref "U3") (pin "11") (pinfunction "PA1_11") (pintype "passive"))
    )
    (net (code "51") (name "unconnected-(U3-PB3-Pad39)") (class "Default")
      (node (ref "U3") (pin "39") (pinfunction "PB3_39") (pintype "passive"))
    )
    (net (code "52") (name "unconnected-(U3-PB8-Pad45)") (class "Default")
      (node (ref "U3") (pin "45") (pinfunction "PB8_45") (pintype "passive"))
    )
    (net (code "53") (name "unconnected-(U3-PB9-Pad46)") (class "Default")
      (node (ref "U3") (pin "46") (pinfunction "PB9_46") (pintype "passive"))
    )
    (net (code "54") (name "unconnected-(U3-PB12-Pad25)") (class "Default")
      (node (ref "U3") (pin "25") (pinfunction "PB12_25") (pintype "passive"))
    )
    (net (code "55") (name "unconnected-(U3-PB15-Pad28)") (class "Default")
      (node (ref "U3") (pin "28") (pinfunction "PB15_28") (pintype "passive"))
    )
    (net (code "56") (name "unconnected-(U3-PC13-Pad2)") (class "Default")
      (node (ref "U3") (pin "2") (pinfunction "PC13_2") (pintype "passive"))
    )
    (net (code "57") (name "unconnected-(U3-UART_CK-Pad29)") (class "Default")
      (node (ref "U3") (pin "29") (pinfunction "UART_CK_29") (pintype "passive"))
    )
    (net (code "58") (name "unconnected-(U3-UART_RX-Pad31)") (class "Default")
      (node (ref "U3") (pin "31") (pinfunction "UART_RX_31") (pintype "passive"))
    )
    (net (code "59") (name "unconnected-(U3-UART_TX-Pad30)") (class "Default")
      (node (ref "U3") (pin "30") (pinfunction "UART_TX_30") (pintype "passive"))
    )
    (net (code "60") (name "unconnected-(U3-VBAT-Pad1)") (class "Default")
      (node (ref "U3") (pin "1") (pinfunction "VBAT_1") (pintype "passive"))
    )
    (net (code "61") (name "unconnected-(U5-FT{slash}OUT-Pad7)") (class "Default")
      (node (ref "U5") (pin "7") (pinfunction "FT/OUT_7") (pintype "passive"))
    )
    (net (code "62") (name "unconnected-(U6-NC-Pad7)") (class "Default")
      (node (ref "U6") (pin "7") (pinfunction "NC_7") (pintype "passive"))
    )
    (net (code "63") (name "unconnected-(U6-~{ALERT}-Pad6)") (class "Default")
      (node (ref "U6") (pin "6") (pinfunction "~{ALERT}_6") (pintype "passive"))
    )
    (net (code "64") (name "unconnected-(U7-IO0-Pad25)") (class "Default")
      (node (ref "U7") (pin "25") (pinfunction "IO0_25") (pintype "passive"))
    )
    (net (code "65") (name "unconnected-(U7-IO2-Pad24)") (class "Default")
      (node (ref "U7") (pin "24") (pinfunction "IO2_24") (pintype "passive"))
    )
    (net (code "66") (name "unconnected-(U7-IO4-Pad26)") (class "Default")
      (node (ref "U7") (pin "26") (pinfunction "IO4_26") (pintype "passive"))
    )
    (net (code "67") (name "unconnected-(U7-IO5-Pad29)") (class "Default")
      (node (ref "U7") (pin "29") (pinfunction "IO5_29") (pintype "passive"))
    )
    (net (code "68") (name "unconnected-(U7-IO12-Pad14)") (class "Default")
      (node (ref "U7") (pin "14") (pinfunction "IO12_14") (pintype "passive"))
    )
    (net (code "69") (name "unconnected-(U7-IO13-Pad16)") (class "Default")
      (node (ref "U7") (pin "16") (pinfunction "IO13_16") (pintype "passive"))
    )
    (net (code "70") (name "unconnected-(U7-IO14-Pad13)") (class "Default")
      (node (ref "U7") (pin "13") (pinfunction "IO14_13") (pintype "passive"))
    )
    (net (code "71") (name "unconnected-(U7-IO15-Pad23)") (class "Default")
      (node (ref "U7") (pin "23") (pinfunction "IO15_23") (pintype "passive"))
    )
    (net (code "72") (name "unconnected-(U7-IO16-Pad27)") (class "Default")
      (node (ref "U7") (pin "27") (pinfunction "IO16_27") (pintype "passive"))
    )
    (net (code "73") (name "unconnected-(U7-IO17-Pad28)") (class "Default")
      (node (ref "U7") (pin "28") (pinfunction "IO17_28") (pintype "passive"))
    )
    (net (code "74") (name "unconnected-(U7-IO18-Pad30)") (class "Default")
      (node (ref "U7") (pin "30") (pinfunction "IO18_30") (pintype "passive"))
    )
    (net (code "75") (name "unconnected-(U7-IO19-Pad31)") (class "Default")
      (node (ref "U7") (pin "31") (pinfunction "IO19_31") (pintype "passive"))
    )
    (net (code "76") (name "unconnected-(U7-IO21-Pad33)") (class "Default")
      (node (ref "U7") (pin "33") (pinfunction "IO21_33") (pintype "passive"))
    )
    (net (code "77") (name "unconnected-(U7-IO22-Pad36)") (class "Default")
      (node (ref "U7") (pin "36") (pinfunction "IO22_36") (pintype "passive"))
    )
    (net (code "78") (name "unconnected-(U7-IO23-Pad37)") (class "Default")
      (node (ref "U7") (pin "37") (pinfunction "IO23_37") (pintype "passive"))
    )
    (net (code "79") (name "unconnected-(U7-IO25-Pad10)") (class "Default")
      (node (ref "U7") (pin "10") (pinfunction "IO25_10") (pintype "passive"))
    )
    (net (code "80") (name "unconnected-(U7-IO26-Pad11)") (class "Default")
      (node (ref "U7") (pin "11") (pinfunction "IO26_11") (pintype "passive"))
    )
    (net (code "81") (name "unconnected-(U7-IO27-Pad12)") (class "Default")
      (node (ref "U7") (pin "12") (pinfunction "IO27_12") (pintype "passive"))
    )
    (net (code "82") (name "unconnected-(U7-IO32-Pad8)") (class "Default")
      (node (ref "U7") (pin "8") (pinfunction "IO32_8") (pintype "passive"))
    )
    (net (code "83") (name "unconnected-(U7-IO33-Pad9)") (class "Default")
      (node (ref "U7") (pin "9") (pinfunction "IO33_9") (pintype "passive"))
    )
    (net (code "84") (name "unconnected-(U7-IO34-Pad6)") (class "Default")
      (node (ref "U7") (pin "6") (pinfunction "IO34_6") (pintype "passive"))
    )
    (net (code "85") (name "unconnected-(U7-IO35-Pad7)") (class "Default")
      (node (ref "U7") (pin "7") (pinfunction "IO35_7") (pintype "passive"))
    )
    (net (code "86") (name "unconnected-(U7-NC-Pad17)") (class "Default")
      (node (ref "U7") (pin "17") (pinfunction "NC_17") (pintype "passive"))
    )
    (net (code "87") (name "unconnected-(U7-NC-Pad18)") (class "Default")
      (node (ref "U7") (pin "18") (pinfunction "NC_18") (pintype "passive"))
    )
    (net (code "88") (name "unconnected-(U7-NC-Pad19)") (class "Default")
      (node (ref "U7") (pin "19") (pinfunction "NC_19") (pintype "passive"))
    )
    (net (code "89") (name "unconnected-(U7-NC-Pad20)") (class "Default")
      (node (ref "U7") (pin "20") (pinfunction "NC_20") (pintype "passive"))
    )
    (net (code "90") (name "unconnected-(U7-NC-Pad21)") (class "Default")
      (node (ref "U7") (pin "21") (pinfunction "NC_21") (pintype "passive"))
    )
    (net (code "91") (name "unconnected-(U7-NC-Pad22)") (class "Default")
      (node (ref "U7") (pin "22") (pinfunction "NC_22") (pintype "passive"))
    )
    (net (code "92") (name "unconnected-(U7-NC-Pad32)") (class "Default")
      (node (ref "U7") (pin "32") (pinfunction "NC_32") (pintype "passive"))
    )
    (net (code "93") (name "unconnected-(U7-SENSOR_VN-Pad5)") (class "Default")
      (node (ref "U7") (pin "5") (pinfunction "SENSOR_VN_5") (pintype "passive"))
    )
    (net (code "94") (name "unconnected-(U7-SENSOR_VP-Pad4)") (class "Default")
      (node (ref "U7") (pin "4") (pinfunction "SENSOR_VP_4") (pintype "passive"))
    )
  )
)
